# MB_interactive.net
KiCad netlist of a schematic drawn in EAGLE
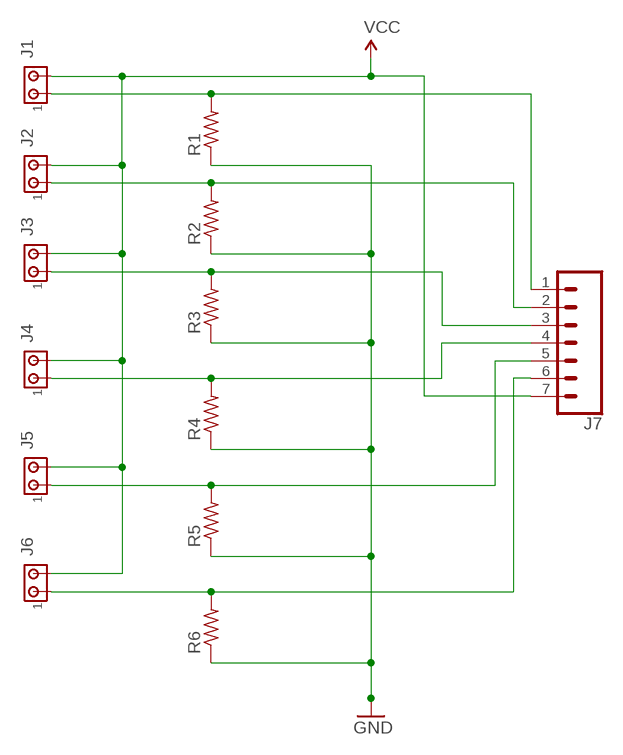
[diagram p0: schematic, sheet 1]

(export (version "E")
  (design (tool "Eeschema 10.0.6"))
  (components
    (comp (ref "J1")
      (value "MTA02-100")
      (footprint "eagle-import:10X02MTA")
      (libsource (lib "eagle-import") (part "MTA02-100"))
    )
    (comp (ref "J2")
      (value "MTA02-100")
      (footprint "eagle-import:10X02MTA")
      (libsource (lib "eagle-import") (part "MTA02-100"))
    )
    (comp (ref "J3")
      (value "MTA02-100")
      (footprint "eagle-import:10X02MTA")
      (libsource (lib "eagle-import") (part "MTA02-100"))
    )
    (comp (ref "J4")
      (value "MTA02-100")
      (footprint "eagle-import:10X02MTA")
      (libsource (lib "eagle-import") (part "MTA02-100"))
    )
    (comp (ref "J5")
      (value "MTA02-100")
      (footprint "eagle-import:10X02MTA")
      (libsource (lib "eagle-import") (part "MTA02-100"))
    )
    (comp (ref "J6")
      (value "MTA02-100")
      (footprint "eagle-import:10X02MTA")
      (libsource (lib "eagle-import") (part "MTA02-100"))
    )
    (comp (ref "J7")
      (value "CONN_07")
      (footprint "eagle-import:1X07")
      (libsource (lib "eagle-import") (part "CONN_07"))
    )
    (comp (ref "R1")
      (value "R-US_0207/7")
      (footprint "eagle-import:0207_7")
      (libsource (lib "eagle-import") (part "R-US_0207/7"))
    )
    (comp (ref "R2")
      (value "R-US_0207/7")
      (footprint "eagle-import:0207_7")
      (libsource (lib "eagle-import") (part "R-US_0207/7"))
    )
    (comp (ref "R3")
      (value "R-US_0207/7")
      (footprint "eagle-import:0207_7")
      (libsource (lib "eagle-import") (part "R-US_0207/7"))
    )
    (comp (ref "R4")
      (value "R-US_0207/7")
      (footprint "eagle-import:0207_7")
      (libsource (lib "eagle-import") (part "R-US_0207/7"))
    )
    (comp (ref "R5")
      (value "R-US_0207/7")
      (footprint "eagle-import:0207_7")
      (libsource (lib "eagle-import") (part "R-US_0207/7"))
    )
    (comp (ref "R6")
      (value "R-US_0207/7")
      (footprint "eagle-import:0207_7")
      (libsource (lib "eagle-import") (part "R-US_0207/7"))
    )
  )
  (nets
    (net (code "1") (name "GND") (class "Default")
      (node (ref "R1") (pin "1") (pinfunction "1_1") (pintype "passive"))
      (node (ref "R2") (pin "1") (pinfunction "1_1") (pintype "passive"))
      (node (ref "R3") (pin "1") (pinfunction "1_1") (pintype "passive"))
      (node (ref "R4") (pin "1") (pinfunction "1_1") (pintype "passive"))
      (node (ref "R5") (pin "1") (pinfunction "1_1") (pintype "passive"))
      (node (ref "R6") (pin "1") (pinfunction "1_1") (pintype "passive"))
    )
    (net (code "2") (name "Net-(J1-Pad1)") (class "Default")
      (node (ref "J1") (pin "1") (pinfunction "1_1") (pintype "passive"))
      (node (ref "J7") (pin "1") (pinfunction "1_1") (pintype "passive"))
      (node (ref "R1") (pin "2") (pinfunction "2_2") (pintype "passive"))
    )
    (net (code "3") (name "Net-(J2-Pad1)") (class "Default")
      (node (ref "J2") (pin "1") (pinfunction "1_1") (pintype "passive"))
      (node (ref "J7") (pin "2") (pinfunction "2_2") (pintype "passive"))
      (node (ref "R2") (pin "2") (pinfunction "2_2") (pintype "passive"))
    )
    (net (code "4") (name "Net-(J3-Pad1)") (class "Default")
      (node (ref "J3") (pin "1") (pinfunction "1_1") (pintype "passive"))
      (node (ref "J7") (pin "3") (pinfunction "3_3") (pintype "passive"))
      (node (ref "R3") (pin "2") (pinfunction "2_2") (pintype "passive"))
    )
    (net (code "5") (name "Net-(J4-Pad1)") (class "Default")
      (node (ref "J4") (pin "1") (pinfunction "1_1") (pintype "passive"))
      (node (ref "J7") (pin "4") (pinfunction "4_4") (pintype "passive"))
      (node (ref "R4") (pin "2") (pinfunction "2_2") (pintype "passive"))
    )
    (net (code "6") (name "Net-(J5-Pad1)") (class "Default")
      (node (ref "J5") (pin "1") (pinfunction "1_1") (pintype "passive"))
      (node (ref "J7") (pin "5") (pinfunction "5_5") (pintype "passive"))
      (node (ref "R5") (pin "2") (pinfunction "2_2") (pintype "passive"))
    )
    (net (code "7") (name "Net-(J6-Pad1)") (class "Default")
      (node (ref "J6") (pin "1") (pinfunction "1_1") (pintype "passive"))
      (node (ref "J7") (pin "6") (pinfunction "6_6") (pintype "passive"))
      (node (ref "R6") (pin "2") (pinfunction "2_2") (pintype "passive"))
    )
    (net (code "8") (name "VCC") (class "Default")
      (node (ref "J1") (pin "2") (pinfunction "2_2") (pintype "passive"))
      (node (ref "J2") (pin "2") (pinfunction "2_2") (pintype "passive"))
      (node (ref "J3") (pin "2") (pinfunction "2_2") (pintype "passive"))
      (node (ref "J4") (pin "2") (pinfunction "2_2") (pintype "passive"))
      (node (ref "J5") (pin "2") (pinfunction "2_2") (pintype "passive"))
      (node (ref "J6") (pin "2") (pinfunction "2_2") (pintype "passive"))
      (node (ref "J7") (pin "7") (pinfunction "7_7") (pintype "passive"))
    )
  )
)
